# Add-OnV20d.net
KiCad netlist of a schematic drawn in EAGLE
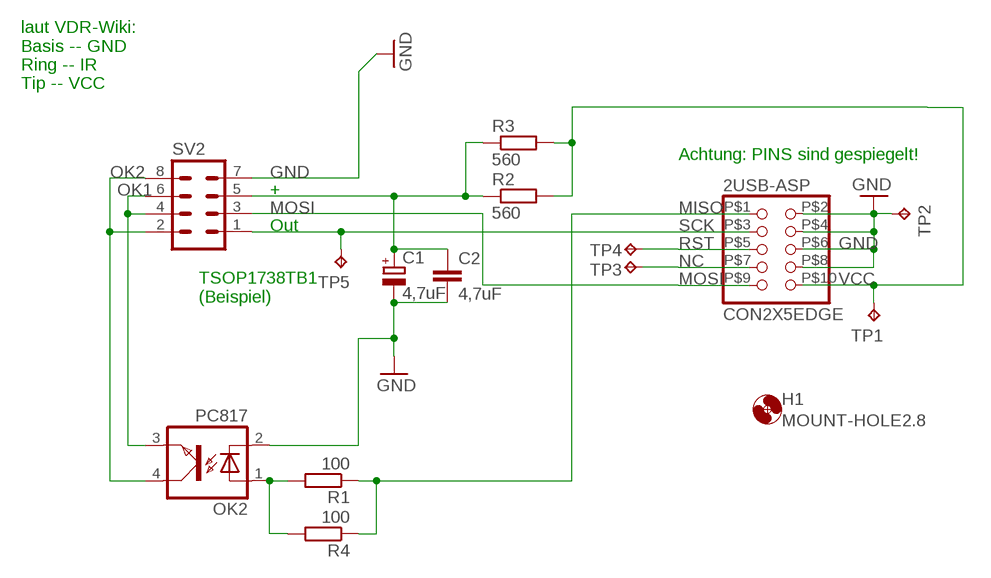
[diagram p0: schematic, sheet 1]

(export (version "E")
  (design (tool "Eeschema 10.0.6"))
  (components
    (comp (ref "2USB-ASP")
      (value "CON2X5EDGE")
      (footprint "eagle-import:CON2X5EDGE")
      (libsource (lib "eagle-import") (part "CON2X5EDGE"))
    )
    (comp (ref "C1")
      (value "4,7uF")
      (footprint "eagle-import:E1,8-4")
      (libsource (lib "eagle-import") (part "CPOL-EUE1.8-4"))
    )
    (comp (ref "C2")
      (value "4,7uF")
      (footprint "eagle-import:C1206K")
      (libsource (lib "eagle-import") (part "C-EUC1206K"))
    )
    (comp (ref "H1")
      (value "MOUNT-HOLE2.8")
      (footprint "eagle-import:2,8")
      (libsource (lib "eagle-import") (part "MOUNT-HOLE2.8"))
    )
    (comp (ref "OK2")
      (value "PC817")
      (footprint "eagle-import:DIL04")
      (fields (field (name "MPN") "PC817X4J000F"))
      (libsource (lib "eagle-import") (part "PC817"))
    )
    (comp (ref "R1")
      (value "100")
      (footprint "eagle-import:0204_7")
      (libsource (lib "eagle-import") (part "R-EU_0204/7"))
    )
    (comp (ref "R2")
      (value "560")
      (footprint "eagle-import:0204_7")
      (libsource (lib "eagle-import") (part "R-EU_0204/7"))
    )
    (comp (ref "R3")
      (value "560")
      (footprint "eagle-import:R0805W")
      (libsource (lib "eagle-import") (part "R-EU_R0805W"))
    )
    (comp (ref "R4")
      (value "100")
      (footprint "eagle-import:R0805W")
      (libsource (lib "eagle-import") (part "R-EU_R0805W"))
    )
    (comp (ref "SV2")
      (value "MA04-2")
      (footprint "eagle-import:MA04-2")
      (libsource (lib "eagle-import") (part "MA04-2"))
    )
    (comp (ref "TP1")
      (value "TPB1,27")
      (footprint "eagle-import:B1,27")
      (libsource (lib "eagle-import") (part "TPB1,27"))
    )
    (comp (ref "TP2")
      (value "TPB1,27")
      (footprint "eagle-import:B1,27")
      (libsource (lib "eagle-import") (part "TPB1,27"))
    )
    (comp (ref "TP3")
      (value "TPB1,27")
      (footprint "eagle-import:B1,27")
      (libsource (lib "eagle-import") (part "TPB1,27"))
    )
    (comp (ref "TP4")
      (value "TPB1,27")
      (footprint "eagle-import:B1,27")
      (libsource (lib "eagle-import") (part "TPB1,27"))
    )
    (comp (ref "TP5")
      (value "TPB1,27")
      (footprint "eagle-import:B1,27")
      (libsource (lib "eagle-import") (part "TPB1,27"))
    )
  )
  (nets
    (net (code "1") (name "/MISO") (class "Default")
      (node (ref "2USB-ASP") (pin "P$1") (pinfunction "1_P$1") (pintype "passive"))
      (node (ref "R1") (pin "1") (pinfunction "1_1") (pintype "passive"))
      (node (ref "R4") (pin "1") (pinfunction "1_1") (pintype "passive"))
    )
    (net (code "2") (name "/MOSI") (class "Default")
      (node (ref "2USB-ASP") (pin "P$9") (pinfunction "9_P$9") (pintype "passive"))
      (node (ref "SV2") (pin "3") (pinfunction "3_3") (pintype "passive"))
    )
    (net (code "3") (name "/NC") (class "Default")
      (node (ref "2USB-ASP") (pin "P$7") (pinfunction "7_P$7") (pintype "passive"))
      (node (ref "TP3") (pin "TP") (pinfunction "TP_TP") (pintype "input"))
    )
    (net (code "4") (name "/OK1") (class "Default")
      (node (ref "OK2") (pin "3") (pinfunction "EMIT_3") (pintype "passive"))
      (node (ref "SV2") (pin "4") (pinfunction "4_4") (pintype "passive"))
      (node (ref "SV2") (pin "6") (pinfunction "6_6") (pintype "passive"))
    )
    (net (code "5") (name "/OK2") (class "Default")
      (node (ref "OK2") (pin "4") (pinfunction "COL_4") (pintype "passive"))
      (node (ref "SV2") (pin "2") (pinfunction "2_2") (pintype "passive"))
      (node (ref "SV2") (pin "8") (pinfunction "8_8") (pintype "passive"))
    )
    (net (code "6") (name "/RST") (class "Default")
      (node (ref "2USB-ASP") (pin "P$5") (pinfunction "5_P$5") (pintype "passive"))
      (node (ref "TP4") (pin "TP") (pinfunction "TP_TP") (pintype "input"))
    )
    (net (code "7") (name "/SCK") (class "Default")
      (node (ref "2USB-ASP") (pin "P$3") (pinfunction "3_P$3") (pintype "passive"))
      (node (ref "SV2") (pin "1") (pinfunction "1_1") (pintype "passive"))
      (node (ref "TP5") (pin "TP") (pinfunction "TP_TP") (pintype "input"))
    )
    (net (code "8") (name "/VCC") (class "Default")
      (node (ref "2USB-ASP") (pin "P$10") (pinfunction "10_P$10") (pintype "passive"))
      (node (ref "R2") (pin "2") (pinfunction "2_2") (pintype "passive"))
      (node (ref "R3") (pin "2") (pinfunction "2_2") (pintype "passive"))
      (node (ref "TP1") (pin "TP") (pinfunction "TP_TP") (pintype "input"))
    )
    (net (code "9") (name "GND") (class "Default")
      (node (ref "2USB-ASP") (pin "P$2") (pinfunction "2_P$2") (pintype "passive"))
      (node (ref "2USB-ASP") (pin "P$4") (pinfunction "4_P$4") (pintype "passive"))
      (node (ref "2USB-ASP") (pin "P$6") (pinfunction "6_P$6") (pintype "passive"))
      (node (ref "2USB-ASP") (pin "P$8") (pinfunction "8_P$8") (pintype "passive"))
      (node (ref "C1") (pin "-") (pinfunction "-_-") (pintype "passive"))
      (node (ref "C2") (pin "2") (pinfunction "2_2") (pintype "passive"))
      (node (ref "OK2") (pin "2") (pinfunction "C_2") (pintype "passive"))
      (node (ref "SV2") (pin "7") (pinfunction "7_7") (pintype "passive"))
      (node (ref "TP2") (pin "TP") (pinfunction "TP_TP") (pintype "input"))
    )
    (net (code "10") (name "Net-(C1-Pad+)") (class "Default")
      (node (ref "C1") (pin "+") (pinfunction "+_+") (pintype "passive"))
      (node (ref "C2") (pin "1") (pinfunction "1_1") (pintype "passive"))
      (node (ref "R2") (pin "1") (pinfunction "1_1") (pintype "passive"))
      (node (ref "R3") (pin "1") (pinfunction "1_1") (pintype "passive"))
      (node (ref "SV2") (pin "5") (pinfunction "5_5") (pintype "passive"))
    )
    (net (code "11") (name "Net-(OK2-A)") (class "Default")
      (node (ref "OK2") (pin "1") (pinfunction "A_1") (pintype "passive"))
      (node (ref "R1") (pin "2") (pinfunction "2_2") (pintype "passive"))
      (node (ref "R4") (pin "2") (pinfunction "2_2") (pintype "passive"))
    )
  )
)
